# ECG_BTLE.net
KiCad netlist of a schematic drawn in EAGLE
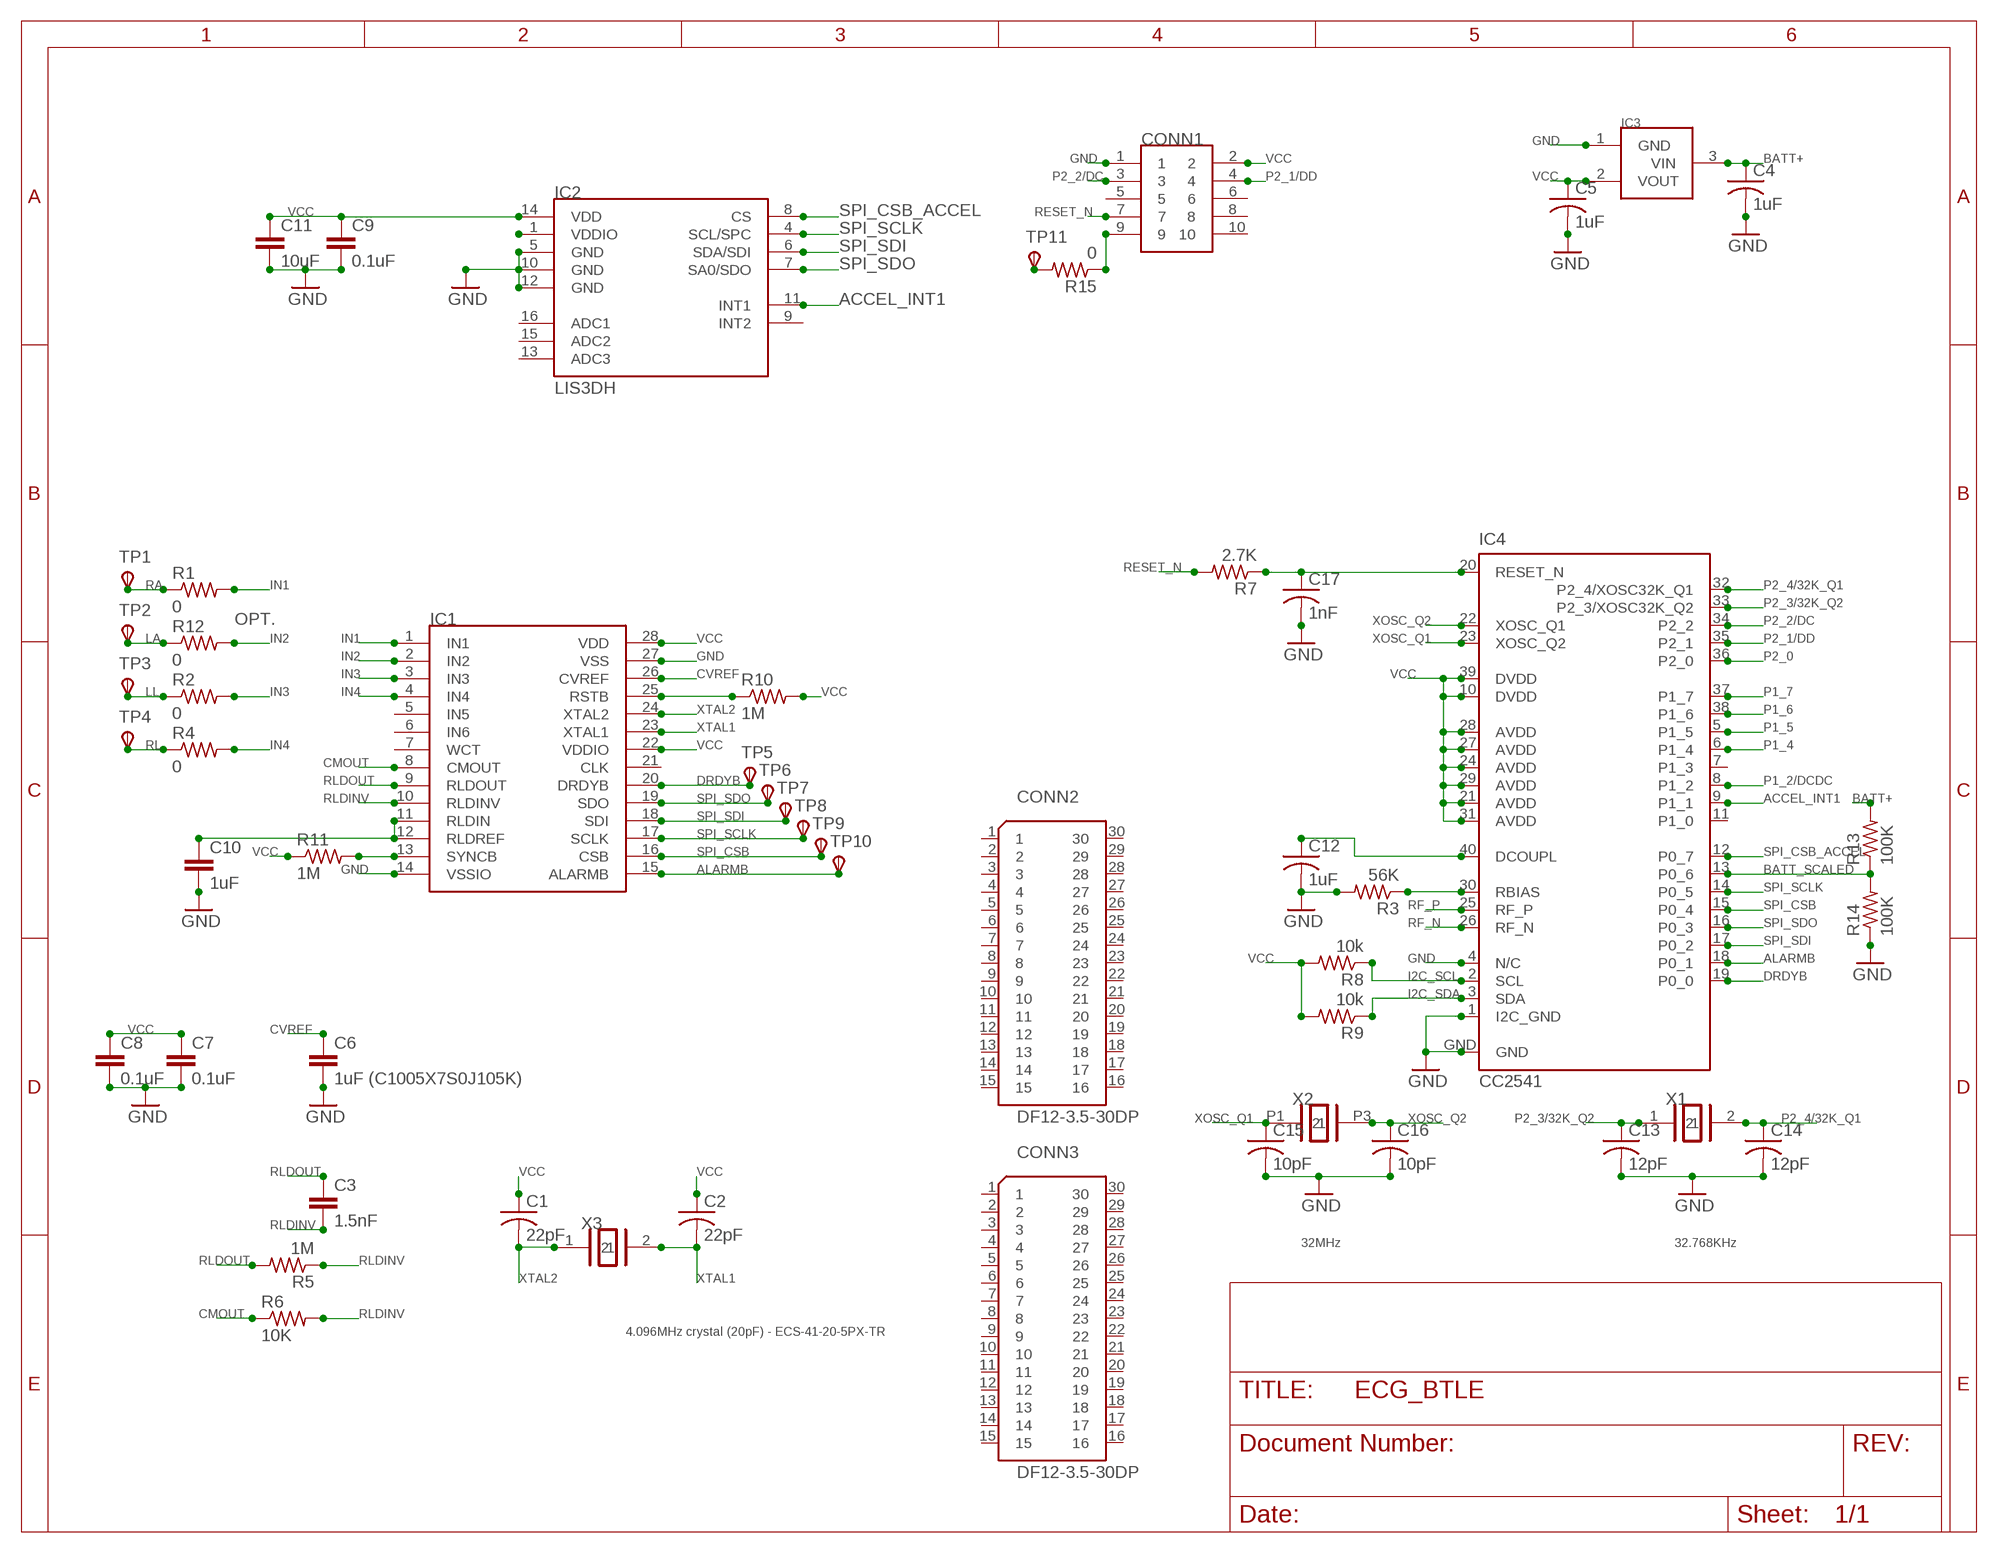
[diagram p0: schematic, sheet 1]

(export (version "E")
  (design (tool "Eeschema 10.0.6"))
  (components
    (comp (ref "C1")
      (value "22pF")
      (footprint "eagle-import:C0201")
      (libsource (lib "eagle-import") (part "C-USC0201"))
    )
    (comp (ref "C2")
      (value "22pF")
      (footprint "eagle-import:C0201")
      (libsource (lib "eagle-import") (part "C-USC0201"))
    )
    (comp (ref "C3")
      (value "1.5nF")
      (footprint "eagle-import:C0402")
      (libsource (lib "eagle-import") (part "C-EUC0402"))
    )
    (comp (ref "C4")
      (value "1uF")
      (footprint "eagle-import:C0201")
      (libsource (lib "eagle-import") (part "C-USC0201"))
    )
    (comp (ref "C5")
      (value "1uF")
      (footprint "eagle-import:C0201")
      (libsource (lib "eagle-import") (part "C-USC0201"))
    )
    (comp (ref "C6")
      (value "1uF (C1005X7S0J105K)")
      (footprint "eagle-import:C0402")
      (libsource (lib "eagle-import") (part "C-EUC0402"))
    )
    (comp (ref "C7")
      (value "0.1uF")
      (footprint "eagle-import:C0402")
      (libsource (lib "eagle-import") (part "C-EUC0402"))
    )
    (comp (ref "C8")
      (value "0.1uF")
      (footprint "eagle-import:C0402")
      (libsource (lib "eagle-import") (part "C-EUC0402"))
    )
    (comp (ref "C9")
      (value "0.1uF")
      (footprint "eagle-import:C0402")
      (libsource (lib "eagle-import") (part "C-EUC0402"))
    )
    (comp (ref "C10")
      (value "1uF")
      (footprint "eagle-import:C0402")
      (libsource (lib "eagle-import") (part "C-EUC0402"))
    )
    (comp (ref "C11")
      (value "10uF")
      (footprint "eagle-import:C0402")
      (libsource (lib "eagle-import") (part "C-EUC0402"))
    )
    (comp (ref "C12")
      (value "1uF")
      (footprint "eagle-import:C0402")
      (libsource (lib "eagle-import") (part "C-USC0402"))
    )
    (comp (ref "C13")
      (value "12pF")
      (footprint "eagle-import:C0201")
      (libsource (lib "eagle-import") (part "C-USC0201"))
    )
    (comp (ref "C14")
      (value "12pF")
      (footprint "eagle-import:C0201")
      (libsource (lib "eagle-import") (part "C-USC0201"))
    )
    (comp (ref "C15")
      (value "10pF")
      (footprint "eagle-import:C0201")
      (libsource (lib "eagle-import") (part "C-USC0201"))
    )
    (comp (ref "C16")
      (value "10pF")
      (footprint "eagle-import:C0201")
      (libsource (lib "eagle-import") (part "C-USC0201"))
    )
    (comp (ref "C17")
      (value "1nF")
      (footprint "eagle-import:C0402")
      (libsource (lib "eagle-import") (part "C-USC0402"))
    )
    (comp (ref "CONN1")
      (value "10POS_1.27MM_SMD")
      (footprint "eagle-import:1.27MM_SMD")
      (libsource (lib "eagle-import") (part "10POS_1.27MM_SMD"))
    )
    (comp (ref "CONN2")
      (value "DF12-3.5-30DP")
      (footprint "eagle-import:DF12-3.5-30DP")
      (libsource (lib "eagle-import") (part "DF12-3.5-30DP"))
    )
    (comp (ref "CONN3")
      (value "DF12-3.5-30DP")
      (footprint "eagle-import:DF12-3.5-30DP")
      (libsource (lib "eagle-import") (part "DF12-3.5-30DP"))
    )
    (comp (ref "IC1")
      (value "ADS1293")
      (footprint "eagle-import:WQFN28")
      (libsource (lib "eagle-import") (part "ADS1293"))
    )
    (comp (ref "IC2")
      (value "LIS3DH")
      (footprint "eagle-import:LGA16-3MM")
      (libsource (lib "eagle-import") (part "LIS3DH"))
    )
    (comp (ref "IC3")
      (value "MCP1703")
      (footprint "eagle-import:SOT23")
      (libsource (lib "eagle-import") (part "MCP1703"))
    )
    (comp (ref "IC4")
      (value "CC2541")
      (footprint "eagle-import:RHA_S-PVQFN-N40")
      (libsource (lib "eagle-import") (part "CC2541"))
    )
    (comp (ref "R1")
      (value "0")
      (footprint "eagle-import:R0402")
      (libsource (lib "eagle-import") (part "resistor_R-US_R0402"))
    )
    (comp (ref "R2")
      (value "0")
      (footprint "eagle-import:R0402")
      (libsource (lib "eagle-import") (part "resistor_R-US_R0402"))
    )
    (comp (ref "R3")
      (value "56K")
      (footprint "eagle-import:R0201")
      (libsource (lib "eagle-import") (part "R-US_R0201"))
    )
    (comp (ref "R4")
      (value "0")
      (footprint "eagle-import:R0402")
      (libsource (lib "eagle-import") (part "resistor_R-US_R0402"))
    )
    (comp (ref "R5")
      (value "1M")
      (footprint "eagle-import:R0603")
      (libsource (lib "eagle-import") (part "resistor_R-US_R0603"))
    )
    (comp (ref "R6")
      (value "10K")
      (footprint "eagle-import:R0402")
      (libsource (lib "eagle-import") (part "resistor_R-US_R0402"))
    )
    (comp (ref "R7")
      (value "2.7K")
      (footprint "eagle-import:R0201")
      (libsource (lib "eagle-import") (part "R-US_R0201"))
    )
    (comp (ref "R8")
      (value "10k")
      (footprint "eagle-import:R0201")
      (libsource (lib "eagle-import") (part "R-US_R0201"))
    )
    (comp (ref "R9")
      (value "10k")
      (footprint "eagle-import:R0201")
      (libsource (lib "eagle-import") (part "R-US_R0201"))
    )
    (comp (ref "R10")
      (value "1M")
      (footprint "eagle-import:R0402")
      (libsource (lib "eagle-import") (part "resistor_R-US_R0402"))
    )
    (comp (ref "R11")
      (value "1M")
      (footprint "eagle-import:R0402")
      (libsource (lib "eagle-import") (part "resistor_R-US_R0402"))
    )
    (comp (ref "R12")
      (value "0")
      (footprint "eagle-import:R0402")
      (libsource (lib "eagle-import") (part "resistor_R-US_R0402"))
    )
    (comp (ref "R13")
      (value "100K")
      (footprint "eagle-import:R0201")
      (libsource (lib "eagle-import") (part "R-US_R0201"))
    )
    (comp (ref "R14")
      (value "100K")
      (footprint "eagle-import:R0201")
      (libsource (lib "eagle-import") (part "R-US_R0201"))
    )
    (comp (ref "R15")
      (value "0")
      (footprint "eagle-import:R0201")
      (libsource (lib "eagle-import") (part "R-US_R0201"))
    )
    (comp (ref "TP1")
      (value "TPSTP08SQ")
      (footprint "eagle-import:TP08SQ")
      (libsource (lib "eagle-import") (part "TPSTP08SQ"))
    )
    (comp (ref "TP2")
      (value "TPSTP08SQ")
      (footprint "eagle-import:TP08SQ")
      (libsource (lib "eagle-import") (part "TPSTP08SQ"))
    )
    (comp (ref "TP3")
      (value "TPSTP08SQ")
      (footprint "eagle-import:TP08SQ")
      (libsource (lib "eagle-import") (part "TPSTP08SQ"))
    )
    (comp (ref "TP4")
      (value "TPSTP08SQ")
      (footprint "eagle-import:TP08SQ")
      (libsource (lib "eagle-import") (part "TPSTP08SQ"))
    )
    (comp (ref "TP5")
      (value "TPSTP08SQ")
      (footprint "eagle-import:TP08SQ")
      (libsource (lib "eagle-import") (part "TPSTP08SQ"))
    )
    (comp (ref "TP6")
      (value "TPSTP08SQ")
      (footprint "eagle-import:TP08SQ")
      (libsource (lib "eagle-import") (part "TPSTP08SQ"))
    )
    (comp (ref "TP7")
      (value "TPSTP08SQ")
      (footprint "eagle-import:TP08SQ")
      (libsource (lib "eagle-import") (part "TPSTP08SQ"))
    )
    (comp (ref "TP8")
      (value "TPSTP08SQ")
      (footprint "eagle-import:TP08SQ")
      (libsource (lib "eagle-import") (part "TPSTP08SQ"))
    )
    (comp (ref "TP9")
      (value "TPSTP08SQ")
      (footprint "eagle-import:TP08SQ")
      (libsource (lib "eagle-import") (part "TPSTP08SQ"))
    )
    (comp (ref "TP10")
      (value "TPSTP08SQ")
      (footprint "eagle-import:TP08SQ")
      (libsource (lib "eagle-import") (part "TPSTP08SQ"))
    )
    (comp (ref "TP11")
      (value "TPSTP08SQ")
      (footprint "eagle-import:TP08SQ")
      (libsource (lib "eagle-import") (part "TPSTP08SQ"))
    )
    (comp (ref "X1")
      (value "XTAL-2SMD")
      (footprint "eagle-import:2-SMD")
      (libsource (lib "eagle-import") (part "XTAL-2SMD"))
    )
    (comp (ref "X2")
      (value "XTAL_403")
      (footprint "eagle-import:4-SMD")
      (libsource (lib "eagle-import") (part "XTAL_403"))
    )
    (comp (ref "X3")
      (value "XTAL-CSM7")
      (footprint "eagle-import:CSM-7")
      (libsource (lib "eagle-import") (part "XTAL-CSM7"))
    )
  )
  (nets
    (net (code "1") (name "/ACCEL_INT1") (class "Default")
      (node (ref "IC2") (pin "11") (pinfunction "INT1_11") (pintype "bidirectional"))
      (node (ref "IC4") (pin "9") (pinfunction "P1_1_9") (pintype "bidirectional"))
    )
    (net (code "2") (name "/ALARMB") (class "Default")
      (node (ref "IC1") (pin "15") (pinfunction "ALARMB_15") (pintype "bidirectional"))
      (node (ref "IC4") (pin "18") (pinfunction "P0_1_18") (pintype "bidirectional"))
      (node (ref "TP10") (pin "TP") (pinfunction "PP_TP") (pintype "input"))
    )
    (net (code "3") (name "/BATT+") (class "Default")
      (node (ref "C4") (pin "1") (pinfunction "1_1") (pintype "passive"))
      (node (ref "IC3") (pin "3") (pinfunction "VIN_3") (pintype "bidirectional"))
      (node (ref "R13") (pin "2") (pinfunction "2_2") (pintype "passive"))
    )
    (net (code "4") (name "/BATT_SCALED") (class "Default")
      (node (ref "IC4") (pin "13") (pinfunction "P0_6_13") (pintype "bidirectional"))
      (node (ref "R13") (pin "1") (pinfunction "1_1") (pintype "passive"))
      (node (ref "R14") (pin "2") (pinfunction "2_2") (pintype "passive"))
    )
    (net (code "5") (name "/CMOUT") (class "Default")
      (node (ref "IC1") (pin "8") (pinfunction "CMOUT_8") (pintype "bidirectional"))
      (node (ref "R6") (pin "1") (pinfunction "1_1") (pintype "passive"))
    )
    (net (code "6") (name "/CVREF") (class "Default")
      (node (ref "C6") (pin "1") (pinfunction "1_1") (pintype "passive"))
      (node (ref "IC1") (pin "26") (pinfunction "CVREF_26") (pintype "bidirectional"))
    )
    (net (code "7") (name "/DRDYB") (class "Default")
      (node (ref "IC1") (pin "20") (pinfunction "DRDYB_20") (pintype "bidirectional"))
      (node (ref "IC4") (pin "19") (pinfunction "P0_0_19") (pintype "bidirectional"))
      (node (ref "TP5") (pin "TP") (pinfunction "PP_TP") (pintype "input"))
    )
    (net (code "8") (name "/I2C_SCL") (class "Default")
      (node (ref "IC4") (pin "2") (pinfunction "SCL_2") (pintype "bidirectional"))
      (node (ref "R8") (pin "1") (pinfunction "1_1") (pintype "passive"))
    )
    (net (code "9") (name "/I2C_SDA") (class "Default")
      (node (ref "IC4") (pin "3") (pinfunction "SDA_3") (pintype "bidirectional"))
      (node (ref "R9") (pin "1") (pinfunction "1_1") (pintype "passive"))
    )
    (net (code "10") (name "/IN1") (class "Default")
      (node (ref "IC1") (pin "1") (pinfunction "IN1_1") (pintype "bidirectional"))
      (node (ref "R1") (pin "2") (pinfunction "2_2") (pintype "passive"))
    )
    (net (code "11") (name "/IN2") (class "Default")
      (node (ref "IC1") (pin "2") (pinfunction "IN2_2") (pintype "bidirectional"))
      (node (ref "R12") (pin "2") (pinfunction "2_2") (pintype "passive"))
    )
    (net (code "12") (name "/IN3") (class "Default")
      (node (ref "IC1") (pin "3") (pinfunction "IN3_3") (pintype "bidirectional"))
      (node (ref "R2") (pin "2") (pinfunction "2_2") (pintype "passive"))
    )
    (net (code "13") (name "/IN4") (class "Default")
      (node (ref "IC1") (pin "4") (pinfunction "IN4_4") (pintype "bidirectional"))
      (node (ref "R4") (pin "2") (pinfunction "2_2") (pintype "passive"))
    )
    (net (code "14") (name "/LA") (class "Default")
      (node (ref "R12") (pin "1") (pinfunction "1_1") (pintype "passive"))
      (node (ref "TP2") (pin "TP") (pinfunction "PP_TP") (pintype "input"))
    )
    (net (code "15") (name "/LL") (class "Default")
      (node (ref "R2") (pin "1") (pinfunction "1_1") (pintype "passive"))
      (node (ref "TP3") (pin "TP") (pinfunction "PP_TP") (pintype "input"))
    )
    (net (code "16") (name "/P1_2{slash}DCDC") (class "Default")
      (node (ref "IC4") (pin "8") (pinfunction "P1_2_8") (pintype "bidirectional"))
    )
    (net (code "17") (name "/P1_4") (class "Default")
      (node (ref "IC4") (pin "6") (pinfunction "P1_4_6") (pintype "bidirectional"))
    )
    (net (code "18") (name "/P1_5") (class "Default")
      (node (ref "IC4") (pin "5") (pinfunction "P1_5_5") (pintype "bidirectional"))
    )
    (net (code "19") (name "/P1_6") (class "Default")
      (node (ref "IC4") (pin "38") (pinfunction "P1_6_38") (pintype "bidirectional"))
    )
    (net (code "20") (name "/P1_7") (class "Default")
      (node (ref "IC4") (pin "37") (pinfunction "P1_7_37") (pintype "bidirectional"))
    )
    (net (code "21") (name "/P2_0") (class "Default")
      (node (ref "IC4") (pin "36") (pinfunction "P2_0_36") (pintype "bidirectional"))
    )
    (net (code "22") (name "/P2_1{slash}DD") (class "Default")
      (node (ref "CONN1") (pin "4") (pinfunction "4_4") (pintype "bidirectional"))
      (node (ref "IC4") (pin "35") (pinfunction "P2_1_35") (pintype "bidirectional"))
    )
    (net (code "23") (name "/P2_2{slash}DC") (class "Default")
      (node (ref "CONN1") (pin "3") (pinfunction "3_3") (pintype "bidirectional"))
      (node (ref "IC4") (pin "34") (pinfunction "P2_2_34") (pintype "bidirectional"))
    )
    (net (code "24") (name "/P2_3{slash}32K_Q2") (class "Default")
      (node (ref "C13") (pin "1") (pinfunction "1_1") (pintype "passive"))
      (node (ref "IC4") (pin "33") (pinfunction "P2_3/XOSC32K_Q2_33") (pintype "bidirectional"))
      (node (ref "X1") (pin "1") (pinfunction "1_1") (pintype "bidirectional"))
    )
    (net (code "25") (name "/P2_4{slash}32K_Q1") (class "Default")
      (node (ref "C14") (pin "1") (pinfunction "1_1") (pintype "passive"))
      (node (ref "IC4") (pin "32") (pinfunction "P2_4/XOSC32K_Q1_32") (pintype "bidirectional"))
      (node (ref "X1") (pin "2") (pinfunction "2_2") (pintype "bidirectional"))
    )
    (net (code "26") (name "/RA") (class "Default")
      (node (ref "R1") (pin "1") (pinfunction "1_1") (pintype "passive"))
      (node (ref "TP1") (pin "TP") (pinfunction "PP_TP") (pintype "input"))
    )
    (net (code "27") (name "/RESET_N") (class "Default")
      (node (ref "CONN1") (pin "7") (pinfunction "7_7") (pintype "bidirectional"))
      (node (ref "R7") (pin "2") (pinfunction "2_2") (pintype "passive"))
    )
    (net (code "28") (name "/RF_N") (class "Default")
      (node (ref "IC4") (pin "26") (pinfunction "RF_N_26") (pintype "bidirectional"))
    )
    (net (code "29") (name "/RF_P") (class "Default")
      (node (ref "IC4") (pin "25") (pinfunction "RF_P_25") (pintype "bidirectional"))
    )
    (net (code "30") (name "/RL") (class "Default")
      (node (ref "R4") (pin "1") (pinfunction "1_1") (pintype "passive"))
      (node (ref "TP4") (pin "TP") (pinfunction "PP_TP") (pintype "input"))
    )
    (net (code "31") (name "/RLDINV") (class "Default")
      (node (ref "C3") (pin "2") (pinfunction "2_2") (pintype "passive"))
      (node (ref "IC1") (pin "10") (pinfunction "RLDINV_10") (pintype "bidirectional"))
      (node (ref "R5") (pin "1") (pinfunction "1_1") (pintype "passive"))
      (node (ref "R6") (pin "2") (pinfunction "2_2") (pintype "passive"))
    )
    (net (code "32") (name "/RLDOUT") (class "Default")
      (node (ref "C3") (pin "1") (pinfunction "1_1") (pintype "passive"))
      (node (ref "IC1") (pin "9") (pinfunction "RLDOUT_9") (pintype "bidirectional"))
      (node (ref "R5") (pin "2") (pinfunction "2_2") (pintype "passive"))
    )
    (net (code "33") (name "/SPI_CSB") (class "Default")
      (node (ref "IC1") (pin "16") (pinfunction "CSB_16") (pintype "bidirectional"))
      (node (ref "IC4") (pin "15") (pinfunction "P0_4_15") (pintype "bidirectional"))
      (node (ref "TP9") (pin "TP") (pinfunction "PP_TP") (pintype "input"))
    )
    (net (code "34") (name "/SPI_CSB_ACCEL") (class "Default")
      (node (ref "IC2") (pin "8") (pinfunction "CS_8") (pintype "bidirectional"))
      (node (ref "IC4") (pin "12") (pinfunction "P0_7_12") (pintype "bidirectional"))
    )
    (net (code "35") (name "/SPI_SCLK") (class "Default")
      (node (ref "IC1") (pin "17") (pinfunction "SCLK_17") (pintype "bidirectional"))
      (node (ref "IC2") (pin "4") (pinfunction "SCL/SPC_4") (pintype "bidirectional"))
      (node (ref "IC4") (pin "14") (pinfunction "P0_5_14") (pintype "bidirectional"))
      (node (ref "TP8") (pin "TP") (pinfunction "PP_TP") (pintype "input"))
    )
    (net (code "36") (name "/SPI_SDI") (class "Default")
      (node (ref "IC1") (pin "18") (pinfunction "SDI_18") (pintype "bidirectional"))
      (node (ref "IC2") (pin "6") (pinfunction "SDA/SDI_6") (pintype "bidirectional"))
      (node (ref "IC4") (pin "17") (pinfunction "P0_2_17") (pintype "bidirectional"))
      (node (ref "TP7") (pin "TP") (pinfunction "PP_TP") (pintype "input"))
    )
    (net (code "37") (name "/SPI_SDO") (class "Default")
      (node (ref "IC1") (pin "19") (pinfunction "SDO_19") (pintype "bidirectional"))
      (node (ref "IC2") (pin "7") (pinfunction "SA0/SDO_7") (pintype "bidirectional"))
      (node (ref "IC4") (pin "16") (pinfunction "P0_3_16") (pintype "bidirectional"))
      (node (ref "TP6") (pin "TP") (pinfunction "PP_TP") (pintype "input"))
    )
    (net (code "38") (name "/VCC") (class "Default")
      (node (ref "C1") (pin "1") (pinfunction "1_1") (pintype "passive"))
      (node (ref "C11") (pin "1") (pinfunction "1_1") (pintype "passive"))
      (node (ref "C2") (pin "1") (pinfunction "1_1") (pintype "passive"))
      (node (ref "C5") (pin "1") (pinfunction "1_1") (pintype "passive"))
      (node (ref "C7") (pin "1") (pinfunction "1_1") (pintype "passive"))
      (node (ref "C8") (pin "1") (pinfunction "1_1") (pintype "passive"))
      (node (ref "C9") (pin "1") (pinfunction "1_1") (pintype "passive"))
      (node (ref "CONN1") (pin "2") (pinfunction "2_2") (pintype "bidirectional"))
      (node (ref "IC1") (pin "22") (pinfunction "VDDIO_22") (pintype "bidirectional"))
      (node (ref "IC1") (pin "28") (pinfunction "VDD_28") (pintype "bidirectional"))
      (node (ref "IC2") (pin "14") (pinfunction "VDD_14") (pintype "bidirectional"))
      (node (ref "IC3") (pin "2") (pinfunction "VOUT_2") (pintype "bidirectional"))
      (node (ref "IC4") (pin "10") (pinfunction "DVDD_10") (pintype "power_in"))
      (node (ref "IC4") (pin "21") (pinfunction "AVDD_21") (pintype "power_in"))
      (node (ref "IC4") (pin "24") (pinfunction "AVDD_24") (pintype "power_in"))
      (node (ref "IC4") (pin "27") (pinfunction "AVDD_27") (pintype "power_in"))
      (node (ref "IC4") (pin "28") (pinfunction "AVDD_28") (pintype "power_in"))
      (node (ref "IC4") (pin "29") (pinfunction "AVDD_29") (pintype "power_in"))
      (node (ref "IC4") (pin "31") (pinfunction "AVDD_31") (pintype "power_in"))
      (node (ref "IC4") (pin "39") (pinfunction "DVDD_39") (pintype "power_in"))
      (node (ref "R10") (pin "2") (pinfunction "2_2") (pintype "passive"))
      (node (ref "R11") (pin "1") (pinfunction "1_1") (pintype "passive"))
      (node (ref "R8") (pin "2") (pinfunction "2_2") (pintype "passive"))
      (node (ref "R9") (pin "2") (pinfunction "2_2") (pintype "passive"))
    )
    (net (code "39") (name "/XOSC_Q1") (class "Default")
      (node (ref "C15") (pin "1") (pinfunction "1_1") (pintype "passive"))
      (node (ref "IC4") (pin "23") (pinfunction "XOSC_Q2_23") (pintype "bidirectional"))
      (node (ref "X2") (pin "P1") (pinfunction "1_P1") (pintype "bidirectional"))
    )
    (net (code "40") (name "/XOSC_Q2") (class "Default")
      (node (ref "C16") (pin "1") (pinfunction "1_1") (pintype "passive"))
      (node (ref "IC4") (pin "22") (pinfunction "XOSC_Q1_22") (pintype "bidirectional"))
      (node (ref "X2") (pin "P3") (pinfunction "2_P3") (pintype "bidirectional"))
    )
    (net (code "41") (name "/XTAL1") (class "Default")
      (node (ref "C2") (pin "2") (pinfunction "2_2") (pintype "passive"))
      (node (ref "IC1") (pin "23") (pinfunction "XTAL1_23") (pintype "bidirectional"))
      (node (ref "X3") (pin "2") (pinfunction "2_2") (pintype "bidirectional"))
    )
    (net (code "42") (name "/XTAL2") (class "Default")
      (node (ref "C1") (pin "2") (pinfunction "2_2") (pintype "passive"))
      (node (ref "IC1") (pin "24") (pinfunction "XTAL2_24") (pintype "bidirectional"))
      (node (ref "X3") (pin "1") (pinfunction "1_1") (pintype "bidirectional"))
    )
    (net (code "43") (name "GND") (class "Default")
      (node (ref "C10") (pin "2") (pinfunction "2_2") (pintype "passive"))
      (node (ref "C11") (pin "2") (pinfunction "2_2") (pintype "passive"))
      (node (ref "C12") (pin "2") (pinfunction "2_2") (pintype "passive"))
      (node (ref "C13") (pin "2") (pinfunction "2_2") (pintype "passive"))
      (node (ref "C14") (pin "2") (pinfunction "2_2") (pintype "passive"))
      (node (ref "C15") (pin "2") (pinfunction "2_2") (pintype "passive"))
      (node (ref "C16") (pin "2") (pinfunction "2_2") (pintype "passive"))
      (node (ref "C17") (pin "2") (pinfunction "2_2") (pintype "passive"))
      (node (ref "C4") (pin "2") (pinfunction "2_2") (pintype "passive"))
      (node (ref "C5") (pin "2") (pinfunction "2_2") (pintype "passive"))
      (node (ref "C6") (pin "2") (pinfunction "2_2") (pintype "passive"))
      (node (ref "C7") (pin "2") (pinfunction "2_2") (pintype "passive"))
      (node (ref "C8") (pin "2") (pinfunction "2_2") (pintype "passive"))
      (node (ref "C9") (pin "2") (pinfunction "2_2") (pintype "passive"))
      (node (ref "CONN1") (pin "1") (pinfunction "1_1") (pintype "bidirectional"))
      (node (ref "IC1") (pin "14") (pinfunction "VSSIO_14") (pintype "bidirectional"))
      (node (ref "IC1") (pin "27") (pinfunction "VSS_27") (pintype "bidirectional"))
      (node (ref "IC2") (pin "10") (pinfunction "GND_10") (pintype "bidirectional"))
      (node (ref "IC2") (pin "12") (pinfunction "GND_12") (pintype "bidirectional"))
      (node (ref "IC2") (pin "5") (pinfunction "GND_5") (pintype "bidirectional"))
      (node (ref "IC3") (pin "1") (pinfunction "GND_1") (pintype "bidirectional"))
      (node (ref "IC4") (pin "1") (pinfunction "I2C_GND_1") (pintype "power_in"))
      (node (ref "IC4") (pin "4") (pinfunction "N/C_4") (pintype "power_in"))
      (node (ref "IC4") (pin "GND") (pinfunction "GND_GND") (pintype "passive"))
      (node (ref "R14") (pin "1") (pinfunction "1_1") (pintype "passive"))
      (node (ref "R3") (pin "2") (pinfunction "2_2") (pintype "passive"))
    )
    (net (code "44") (name "Net-(CONN1-Pad9)") (class "Default")
      (node (ref "CONN1") (pin "9") (pinfunction "9_9") (pintype "bidirectional"))
      (node (ref "R15") (pin "1") (pinfunction "1_1") (pintype "passive"))
    )
    (net (code "45") (name "Net-(IC1-RLDIN)") (class "Default")
      (node (ref "C10") (pin "1") (pinfunction "1_1") (pintype "passive"))
      (node (ref "IC1") (pin "11") (pinfunction "RLDIN_11") (pintype "bidirectional"))
      (node (ref "IC1") (pin "12") (pinfunction "RLDREF_12") (pintype "bidirectional"))
    )
    (net (code "46") (name "Net-(IC1-RSTB)") (class "Default")
      (node (ref "IC1") (pin "25") (pinfunction "RSTB_25") (pintype "bidirectional"))
      (node (ref "R10") (pin "1") (pinfunction "1_1") (pintype "passive"))
    )
    (net (code "47") (name "Net-(IC1-SYNCB)") (class "Default")
      (node (ref "IC1") (pin "13") (pinfunction "SYNCB_13") (pintype "bidirectional"))
      (node (ref "R11") (pin "2") (pinfunction "2_2") (pintype "passive"))
    )
    (net (code "48") (name "Net-(IC4-DCOUPL)") (class "Default")
      (node (ref "C12") (pin "1") (pinfunction "1_1") (pintype "passive"))
      (node (ref "IC4") (pin "40") (pinfunction "DCOUPL_40") (pintype "power_in"))
    )
    (net (code "49") (name "Net-(IC4-RBIAS)") (class "Default")
      (node (ref "IC4") (pin "30") (pinfunction "RBIAS_30") (pintype "bidirectional"))
      (node (ref "R3") (pin "1") (pinfunction "1_1") (pintype "passive"))
    )
    (net (code "50") (name "Net-(IC4-RESET_N)") (class "Default")
      (node (ref "C17") (pin "1") (pinfunction "1_1") (pintype "passive"))
      (node (ref "IC4") (pin "20") (pinfunction "RESET_N_20") (pintype "input"))
      (node (ref "R7") (pin "1") (pinfunction "1_1") (pintype "passive"))
    )
    (net (code "51") (name "Net-(TP11-PP)") (class "Default")
      (node (ref "R15") (pin "2") (pinfunction "2_2") (pintype "passive"))
      (node (ref "TP11") (pin "TP") (pinfunction "PP_TP") (pintype "input"))
    )
    (net (code "52") (name "unconnected-(CONN1-Pad5)") (class "Default")
      (node (ref "CONN1") (pin "5") (pinfunction "5_5") (pintype "bidirectional"))
    )
    (net (code "53") (name "unconnected-(CONN1-Pad6)") (class "Default")
      (node (ref "CONN1") (pin "6") (pinfunction "6_6") (pintype "bidirectional"))
    )
    (net (code "54") (name "unconnected-(CONN1-Pad8)") (class "Default")
      (node (ref "CONN1") (pin "8") (pinfunction "8_8") (pintype "bidirectional"))
    )
    (net (code "55") (name "unconnected-(CONN1-Pad10)") (class "Default")
      (node (ref "CONN1") (pin "10") (pinfunction "10_10") (pintype "bidirectional"))
    )
    (net (code "56") (name "unconnected-(CONN2-Pad1)") (class "Default")
      (node (ref "CONN2") (pin "1") (pinfunction "1_1") (pintype "bidirectional"))
    )
    (net (code "57") (name "unconnected-(CONN2-Pad2)") (class "Default")
      (node (ref "CONN2") (pin "2") (pinfunction "2_2") (pintype "bidirectional"))
    )
    (net (code "58") (name "unconnected-(CONN2-Pad3)") (class "Default")
      (node (ref "CONN2") (pin "3") (pinfunction "3_3") (pintype "bidirectional"))
    )
    (net (code "59") (name "unconnected-(CONN2-Pad4)") (class "Default")
      (node (ref "CONN2") (pin "4") (pinfunction "4_4") (pintype "bidirectional"))
    )
    (net (code "60") (name "unconnected-(CONN2-Pad5)") (class "Default")
      (node (ref "CONN2") (pin "5") (pinfunction "5_5") (pintype "bidirectional"))
    )
    (net (code "61") (name "unconnected-(CONN2-Pad6)") (class "Default")
      (node (ref "CONN2") (pin "6") (pinfunction "6_6") (pintype "bidirectional"))
    )
    (net (code "62") (name "unconnected-(CONN2-Pad7)") (class "Default")
      (node (ref "CONN2") (pin "7") (pinfunction "7_7") (pintype "bidirectional"))
    )
    (net (code "63") (name "unconnected-(CONN2-Pad8)") (class "Default")
      (node (ref "CONN2") (pin "8") (pinfunction "8_8") (pintype "bidirectional"))
    )
    (net (code "64") (name "unconnected-(CONN2-Pad9)") (class "Default")
      (node (ref "CONN2") (pin "9") (pinfunction "9_9") (pintype "bidirectional"))
    )
    (net (code "65") (name "unconnected-(CONN2-Pad10)") (class "Default")
      (node (ref "CONN2") (pin "10") (pinfunction "10_10") (pintype "bidirectional"))
    )
    (net (code "66") (name "unconnected-(CONN2-Pad11)") (class "Default")
      (node (ref "CONN2") (pin "11") (pinfunction "11_11") (pintype "bidirectional"))
    )
    (net (code "67") (name "unconnected-(CONN2-Pad12)") (class "Default")
      (node (ref "CONN2") (pin "12") (pinfunction "12_12") (pintype "bidirectional"))
    )
    (net (code "68") (name "unconnected-(CONN2-Pad13)") (class "Default")
      (node (ref "CONN2") (pin "13") (pinfunction "13_13") (pintype "bidirectional"))
    )
    (net (code "69") (name "unconnected-(CONN2-Pad14)") (class "Default")
      (node (ref "CONN2") (pin "14") (pinfunction "14_14") (pintype "bidirectional"))
    )
    (net (code "70") (name "unconnected-(CONN2-Pad15)") (class "Default")
      (node (ref "CONN2") (pin "15") (pinfunction "15_15") (pintype "bidirectional"))
    )
    (net (code "71") (name "unconnected-(CONN2-Pad16)") (class "Default")
      (node (ref "CONN2") (pin "16") (pinfunction "16_16") (pintype "bidirectional"))
    )
    (net (code "72") (name "unconnected-(CONN2-Pad17)") (class "Default")
      (node (ref "CONN2") (pin "17") (pinfunction "17_17") (pintype "bidirectional"))
    )
    (net (code "73") (name "unconnected-(CONN2-Pad18)") (class "Default")
      (node (ref "CONN2") (pin "18") (pinfunction "18_18") (pintype "bidirectional"))
    )
    (net (code "74") (name "unconnected-(CONN2-Pad19)") (class "Default")
      (node (ref "CONN2") (pin "19") (pinfunction "19_19") (pintype "bidirectional"))
    )
    (net (code "75") (name "unconnected-(CONN2-Pad20)") (class "Default")
      (node (ref "CONN2") (pin "20") (pinfunction "20_20") (pintype "bidirectional"))
    )
    (net (code "76") (name "unconnected-(CONN2-Pad21)") (class "Default")
      (node (ref "CONN2") (pin "21") (pinfunction "21_21") (pintype "bidirectional"))
    )
    (net (code "77") (name "unconnected-(CONN2-Pad22)") (class "Default")
      (node (ref "CONN2") (pin "22") (pinfunction "22_22") (pintype "bidirectional"))
    )
    (net (code "78") (name "unconnected-(CONN2-Pad23)") (class "Default")
      (node (ref "CONN2") (pin "23") (pinfunction "23_23") (pintype "bidirectional"))
    )
    (net (code "79") (name "unconnected-(CONN2-Pad24)") (class "Default")
      (node (ref "CONN2") (pin "24") (pinfunction "24_24") (pintype "bidirectional"))
    )
    (net (code "80") (name "unconnected-(CONN2-Pad25)") (class "Default")
      (node (ref "CONN2") (pin "25") (pinfunction "25_25") (pintype "bidirectional"))
    )
    (net (code "81") (name "unconnected-(CONN2-Pad26)") (class "Default")
      (node (ref "CONN2") (pin "26") (pinfunction "26_26") (pintype "bidirectional"))
    )
    (net (code "82") (name "unconnected-(CONN2-Pad27)") (class "Default")
      (node (ref "CONN2") (pin "27") (pinfunction "27_27") (pintype "bidirectional"))
    )
    (net (code "83") (name "unconnected-(CONN2-Pad28)") (class "Default")
      (node (ref "CONN2") (pin "28") (pinfunction "28_28") (pintype "bidirectional"))
    )
    (net (code "84") (name "unconnected-(CONN2-Pad29)") (class "Default")
      (node (ref "CONN2") (pin "29") (pinfunction "29_29") (pintype "bidirectional"))
    )
    (net (code "85") (name "unconnected-(CONN2-Pad30)") (class "Default")
      (node (ref "CONN2") (pin "30") (pinfunction "30_30") (pintype "bidirectional"))
    )
    (net (code "86") (name "unconnected-(CONN3-Pad1)") (class "Default")
      (node (ref "CONN3") (pin "1") (pinfunction "1_1") (pintype "bidirectional"))
    )
    (net (code "87") (name "unconnected-(CONN3-Pad2)") (class "Default")
      (node (ref "CONN3") (pin "2") (pinfunction "2_2") (pintype "bidirectional"))
    )
    (net (code "88") (name "unconnected-(CONN3-Pad3)") (class "Default")
      (node (ref "CONN3") (pin "3") (pinfunction "3_3") (pintype "bidirectional"))
    )
    (net (code "89") (name "unconnected-(CONN3-Pad4)") (class "Default")
      (node (ref "CONN3") (pin "4") (pinfunction "4_4") (pintype "bidirectional"))
    )
    (net (code "90") (name "unconnected-(CONN3-Pad5)") (class "Default")
      (node (ref "CONN3") (pin "5") (pinfunction "5_5") (pintype "bidirectional"))
    )
    (net (code "91") (name "unconnected-(CONN3-Pad6)") (class "Default")
      (node (ref "CONN3") (pin "6") (pinfunction "6_6") (pintype "bidirectional"))
    )
    (net (code "92") (name "unconnected-(CONN3-Pad7)") (class "Default")
      (node (ref "CONN3") (pin "7") (pinfunction "7_7") (pintype "bidirectional"))
    )
    (net (code "93") (name "unconnected-(CONN3-Pad8)") (class "Default")
      (node (ref "CONN3") (pin "8") (pinfunction "8_8") (pintype "bidirectional"))
    )
    (net (code "94") (name "unconnected-(CONN3-Pad9)") (class "Default")
      (node (ref "CONN3") (pin "9") (pinfunction "9_9") (pintype "bidirectional"))
    )
    (net (code "95") (name "unconnected-(CONN3-Pad10)") (class "Default")
      (node (ref "CONN3") (pin "10") (pinfunction "10_10") (pintype "bidirectional"))
    )
    (net (code "96") (name "unconnected-(CONN3-Pad11)") (class "Default")
      (node (ref "CONN3") (pin "11") (pinfunction "11_11") (pintype "bidirectional"))
    )
    (net (code "97") (name "unconnected-(CONN3-Pad12)") (class "Default")
      (node (ref "CONN3") (pin "12") (pinfunction "12_12") (pintype "bidirectional"))
    )
    (net (code "98") (name "unconnected-(CONN3-Pad13)") (class "Default")
      (node (ref "CONN3") (pin "13") (pinfunction "13_13") (pintype "bidirectional"))
    )
    (net (code "99") (name "unconnected-(CONN3-Pad14)") (class "Default")
      (node (ref "CONN3") (pin "14") (pinfunction "14_14") (pintype "bidirectional"))
    )
    (net (code "100") (name "unconnected-(CONN3-Pad15)") (class "Default")
      (node (ref "CONN3") (pin "15") (pinfunction "15_15") (pintype "bidirectional"))
    )
    (net (code "101") (name "unconnected-(CONN3-Pad16)") (class "Default")
      (node (ref "CONN3") (pin "16") (pinfunction "16_16") (pintype "bidirectional"))
    )
    (net (code "102") (name "unconnected-(CONN3-Pad17)") (class "Default")
      (node (ref "CONN3") (pin "17") (pinfunction "17_17") (pintype "bidirectional"))
    )
    (net (code "103") (name "unconnected-(CONN3-Pad18)") (class "Default")
      (node (ref "CONN3") (pin "18") (pinfunction "18_18") (pintype "bidirectional"))
    )
    (net (code "104") (name "unconnected-(CONN3-Pad19)") (class "Default")
      (node (ref "CONN3") (pin "19") (pinfunction "19_19") (pintype "bidirectional"))
    )
    (net (code "105") (name "unconnected-(CONN3-Pad20)") (class "Default")
      (node (ref "CONN3") (pin "20") (pinfunction "20_20") (pintype "bidirectional"))
    )
    (net (code "106") (name "unconnected-(CONN3-Pad21)") (class "Default")
      (node (ref "CONN3") (pin "21") (pinfunction "21_21") (pintype "bidirectional"))
    )
    (net (code "107") (name "unconnected-(CONN3-Pad22)") (class "Default")
      (node (ref "CONN3") (pin "22") (pinfunction "22_22") (pintype "bidirectional"))
    )
    (net (code "108") (name "unconnected-(CONN3-Pad23)") (class "Default")
      (node (ref "CONN3") (pin "23") (pinfunction "23_23") (pintype "bidirectional"))
    )
    (net (code "109") (name "unconnected-(CONN3-Pad24)") (class "Default")
      (node (ref "CONN3") (pin "24") (pinfunction "24_24") (pintype "bidirectional"))
    )
    (net (code "110") (name "unconnected-(CONN3-Pad25)") (class "Default")
      (node (ref "CONN3") (pin "25") (pinfunction "25_25") (pintype "bidirectional"))
    )
    (net (code "111") (name "unconnected-(CONN3-Pad26)") (class "Default")
      (node (ref "CONN3") (pin "26") (pinfunction "26_26") (pintype "bidirectional"))
    )
    (net (code "112") (name "unconnected-(CONN3-Pad27)") (class "Default")
      (node (ref "CONN3") (pin "27") (pinfunction "27_27") (pintype "bidirectional"))
    )
    (net (code "113") (name "unconnected-(CONN3-Pad28)") (class "Default")
      (node (ref "CONN3") (pin "28") (pinfunction "28_28") (pintype "bidirectional"))
    )
    (net (code "114") (name "unconnected-(CONN3-Pad29)") (class "Default")
      (node (ref "CONN3") (pin "29") (pinfunction "29_29") (pintype "bidirectional"))
    )
    (net (code "115") (name "unconnected-(CONN3-Pad30)") (class "Default")
      (node (ref "CONN3") (pin "30") (pinfunction "30_30") (pintype "bidirectional"))
    )
    (net (code "116") (name "unconnected-(IC1-CLK-Pad21)") (class "Default")
      (node (ref "IC1") (pin "21") (pinfunction "CLK_21") (pintype "bidirectional"))
    )
    (net (code "117") (name "unconnected-(IC1-IN5-Pad5)") (class "Default")
      (node (ref "IC1") (pin "5") (pinfunction "IN5_5") (pintype "bidirectional"))
    )
    (net (code "118") (name "unconnected-(IC1-IN6-Pad6)") (class "Default")
      (node (ref "IC1") (pin "6") (pinfunction "IN6_6") (pintype "bidirectional"))
    )
    (net (code "119") (name "unconnected-(IC1-WCT-Pad7)") (class "Default")
      (node (ref "IC1") (pin "7") (pinfunction "WCT_7") (pintype "bidirectional"))
    )
    (net (code "120") (name "unconnected-(IC2-ADC1-Pad16)") (class "Default")
      (node (ref "IC2") (pin "16") (pinfunction "ADC1_16") (pintype "bidirectional"))
    )
    (net (code "121") (name "unconnected-(IC2-ADC2-Pad15)") (class "Default")
      (node (ref "IC2") (pin "15") (pinfunction "ADC2_15") (pintype "bidirectional"))
    )
    (net (code "122") (name "unconnected-(IC2-ADC3-Pad13)") (class "Default")
      (node (ref "IC2") (pin "13") (pinfunction "ADC3_13") (pintype "bidirectional"))
    )
    (net (code "123") (name "unconnected-(IC2-INT2-Pad9)") (class "Default")
      (node (ref "IC2") (pin "9") (pinfunction "INT2_9") (pintype "bidirectional"))
    )
    (net (code "124") (name "unconnected-(IC2-VDDIO-Pad1)") (class "Default")
      (node (ref "IC2") (pin "1") (pinfunction "VDDIO_1") (pintype "bidirectional"))
    )
    (net (code "125") (name "unconnected-(IC4-P1_0-Pad11)") (class "Default")
      (node (ref "IC4") (pin "11") (pinfunction "P1_0_11") (pintype "bidirectional"))
    )
    (net (code "126") (name "unconnected-(IC4-P1_3-Pad7)") (class "Default")
      (node (ref "IC4") (pin "7") (pinfunction "P1_3_7") (pintype "bidirectional"))
    )
  )
)
